# Schematic.net
KiCad netlist of a schematic drawn in Altium Designer
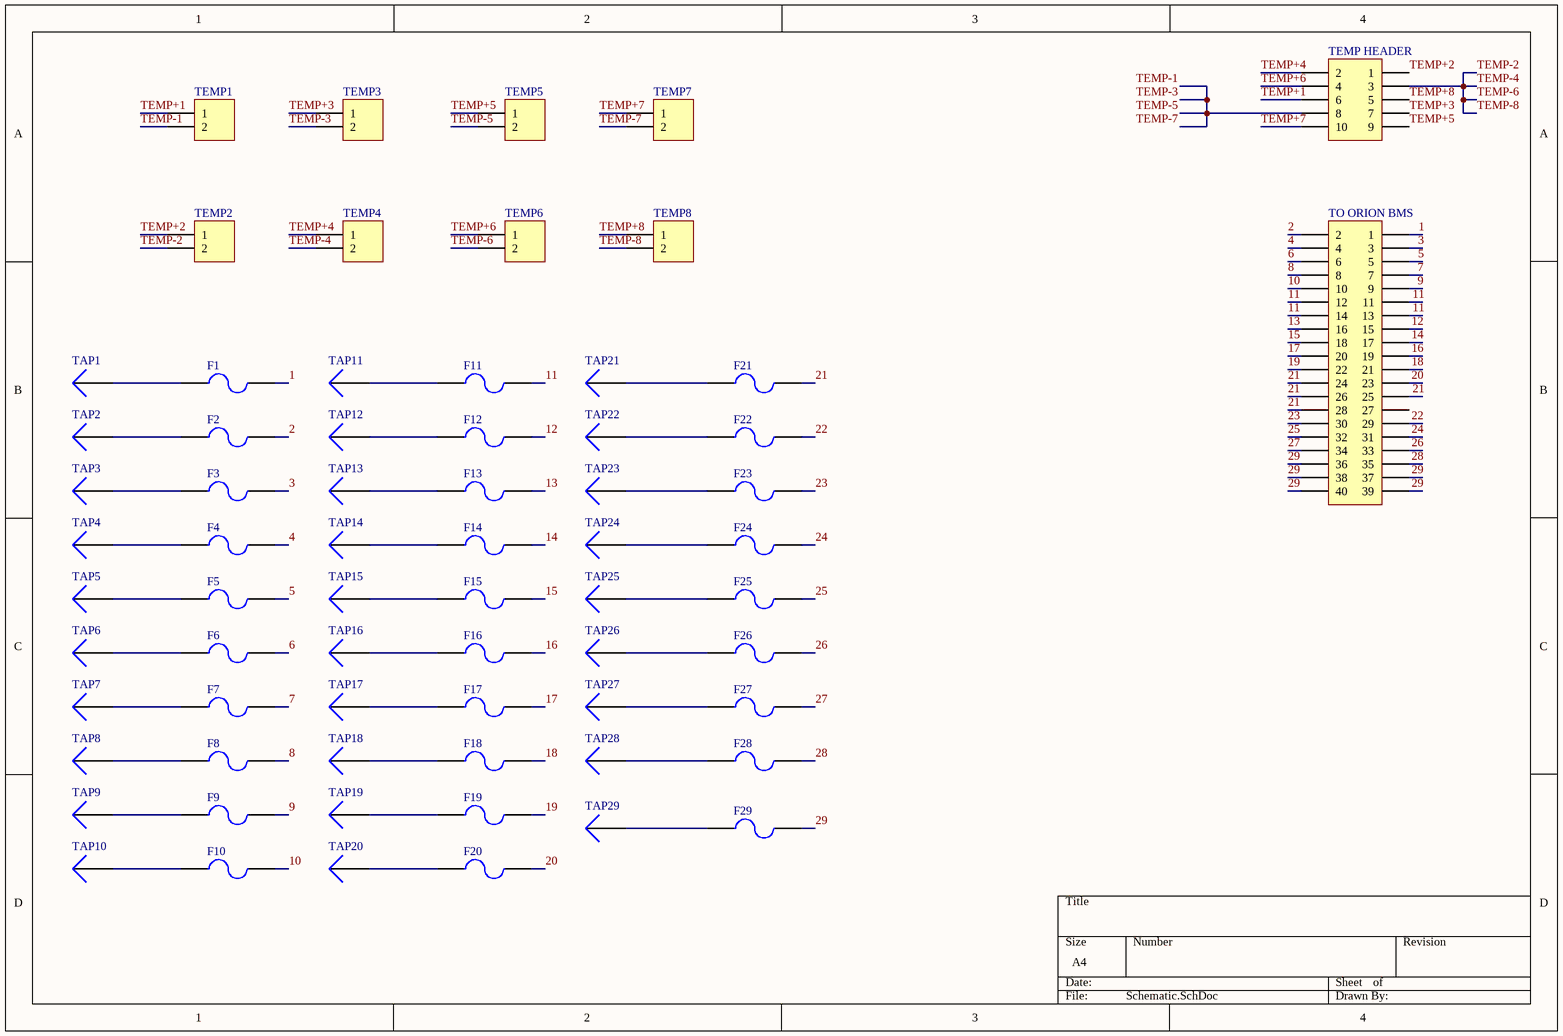
[diagram p0: Schematic.SchDoc]

(export (version "E")
  (design (tool "Eeschema 10.0.6"))
  (components
    (comp (ref "F1")
      (value "~")
      (footprint "0451Series_LTF")
      (description "FUSE BOARD MNT 750MA 125VAC/VDC")
      (fields (field (name "PART NUMBER") "0154.750MRL") (field (name "MANUFACTURER") "Littelfuse Inc."))
      (libsource (lib "ts_standard_library") (part "Fuse"))
    )
    (comp (ref "F2")
      (value "~")
      (footprint "0451Series_LTF")
      (description "FUSE BOARD MNT 750MA 125VAC/VDC")
      (fields (field (name "PART NUMBER") "0154.750MRL") (field (name "MANUFACTURER") "Littelfuse Inc."))
      (libsource (lib "ts_standard_library") (part "Fuse"))
    )
    (comp (ref "F3")
      (value "~")
      (footprint "0451Series_LTF")
      (description "FUSE BOARD MNT 750MA 125VAC/VDC")
      (fields (field (name "PART NUMBER") "0154.750MRL") (field (name "MANUFACTURER") "Littelfuse Inc."))
      (libsource (lib "ts_standard_library") (part "Fuse"))
    )
    (comp (ref "F4")
      (value "~")
      (footprint "0451Series_LTF")
      (description "FUSE BOARD MNT 750MA 125VAC/VDC")
      (fields (field (name "PART NUMBER") "0154.750MRL") (field (name "MANUFACTURER") "Littelfuse Inc."))
      (libsource (lib "ts_standard_library") (part "Fuse"))
    )
    (comp (ref "F5")
      (value "~")
      (footprint "0451Series_LTF")
      (description "FUSE BOARD MNT 750MA 125VAC/VDC")
      (fields (field (name "PART NUMBER") "0154.750MRL") (field (name "MANUFACTURER") "Littelfuse Inc."))
      (libsource (lib "ts_standard_library") (part "Fuse"))
    )
    (comp (ref "F6")
      (value "~")
      (footprint "0451Series_LTF")
      (description "FUSE BOARD MNT 750MA 125VAC/VDC")
      (fields (field (name "PART NUMBER") "0154.750MRL") (field (name "MANUFACTURER") "Littelfuse Inc."))
      (libsource (lib "ts_standard_library") (part "Fuse"))
    )
    (comp (ref "F7")
      (value "~")
      (footprint "0451Series_LTF")
      (description "FUSE BOARD MNT 750MA 125VAC/VDC")
      (fields (field (name "PART NUMBER") "0154.750MRL") (field (name "MANUFACTURER") "Littelfuse Inc."))
      (libsource (lib "ts_standard_library") (part "Fuse"))
    )
    (comp (ref "F8")
      (value "~")
      (footprint "0451Series_LTF")
      (description "FUSE BOARD MNT 750MA 125VAC/VDC")
      (fields (field (name "PART NUMBER") "0154.750MRL") (field (name "MANUFACTURER") "Littelfuse Inc."))
      (libsource (lib "ts_standard_library") (part "Fuse"))
    )
    (comp (ref "F9")
      (value "~")
      (footprint "0451Series_LTF")
      (description "FUSE BOARD MNT 750MA 125VAC/VDC")
      (fields (field (name "PART NUMBER") "0154.750MRL") (field (name "MANUFACTURER") "Littelfuse Inc."))
      (libsource (lib "ts_standard_library") (part "Fuse"))
    )
    (comp (ref "F10")
      (value "~")
      (footprint "0451Series_LTF")
      (description "FUSE BOARD MNT 750MA 125VAC/VDC")
      (fields (field (name "PART NUMBER") "0154.750MRL") (field (name "MANUFACTURER") "Littelfuse Inc."))
      (libsource (lib "ts_standard_library") (part "Fuse"))
    )
    (comp (ref "F11")
      (value "~")
      (footprint "0451Series_LTF")
      (description "FUSE BOARD MNT 750MA 125VAC/VDC")
      (fields (field (name "PART NUMBER") "0154.750MRL") (field (name "MANUFACTURER") "Littelfuse Inc."))
      (libsource (lib "ts_standard_library") (part "Fuse"))
    )
    (comp (ref "F12")
      (value "~")
      (footprint "0451Series_LTF")
      (description "FUSE BOARD MNT 750MA 125VAC/VDC")
      (fields (field (name "PART NUMBER") "0154.750MRL") (field (name "MANUFACTURER") "Littelfuse Inc."))
      (libsource (lib "ts_standard_library") (part "Fuse"))
    )
    (comp (ref "F13")
      (value "~")
      (footprint "0451Series_LTF")
      (description "FUSE BOARD MNT 750MA 125VAC/VDC")
      (fields (field (name "PART NUMBER") "0154.750MRL") (field (name "MANUFACTURER") "Littelfuse Inc."))
      (libsource (lib "ts_standard_library") (part "Fuse"))
    )
    (comp (ref "F14")
      (value "~")
      (footprint "0451Series_LTF")
      (description "FUSE BOARD MNT 750MA 125VAC/VDC")
      (fields (field (name "PART NUMBER") "0154.750MRL") (field (name "MANUFACTURER") "Littelfuse Inc."))
      (libsource (lib "ts_standard_library") (part "Fuse"))
    )
    (comp (ref "F15")
      (value "~")
      (footprint "0451Series_LTF")
      (description "FUSE BOARD MNT 750MA 125VAC/VDC")
      (fields (field (name "PART NUMBER") "0154.750MRL") (field (name "MANUFACTURER") "Littelfuse Inc."))
      (libsource (lib "ts_standard_library") (part "Fuse"))
    )
    (comp (ref "F16")
      (value "~")
      (footprint "0451Series_LTF")
      (description "FUSE BOARD MNT 750MA 125VAC/VDC")
      (fields (field (name "PART NUMBER") "0154.750MRL") (field (name "MANUFACTURER") "Littelfuse Inc."))
      (libsource (lib "ts_standard_library") (part "Fuse"))
    )
    (comp (ref "F17")
      (value "~")
      (footprint "0451Series_LTF")
      (description "FUSE BOARD MNT 750MA 125VAC/VDC")
      (fields (field (name "PART NUMBER") "0154.750MRL") (field (name "MANUFACTURER") "Littelfuse Inc."))
      (libsource (lib "ts_standard_library") (part "Fuse"))
    )
    (comp (ref "F18")
      (value "~")
      (footprint "0451Series_LTF")
      (description "FUSE BOARD MNT 750MA 125VAC/VDC")
      (fields (field (name "PART NUMBER") "0154.750MRL") (field (name "MANUFACTURER") "Littelfuse Inc."))
      (libsource (lib "ts_standard_library") (part "Fuse"))
    )
    (comp (ref "F19")
      (value "~")
      (footprint "0451Series_LTF")
      (description "FUSE BOARD MNT 750MA 125VAC/VDC")
      (fields (field (name "PART NUMBER") "0154.750MRL") (field (name "MANUFACTURER") "Littelfuse Inc."))
      (libsource (lib "ts_standard_library") (part "Fuse"))
    )
    (comp (ref "F20")
      (value "~")
      (footprint "0451Series_LTF")
      (description "FUSE BOARD MNT 750MA 125VAC/VDC")
      (fields (field (name "PART NUMBER") "0154.750MRL") (field (name "MANUFACTURER") "Littelfuse Inc."))
      (libsource (lib "ts_standard_library") (part "Fuse"))
    )
    (comp (ref "F21")
      (value "~")
      (footprint "0451Series_LTF")
      (description "FUSE BOARD MNT 750MA 125VAC/VDC")
      (fields (field (name "PART NUMBER") "0154.750MRL") (field (name "MANUFACTURER") "Littelfuse Inc."))
      (libsource (lib "ts_standard_library") (part "Fuse"))
    )
    (comp (ref "F22")
      (value "~")
      (footprint "0451Series_LTF")
      (description "FUSE BOARD MNT 750MA 125VAC/VDC")
      (fields (field (name "PART NUMBER") "0154.750MRL") (field (name "MANUFACTURER") "Littelfuse Inc."))
      (libsource (lib "ts_standard_library") (part "Fuse"))
    )
    (comp (ref "F23")
      (value "~")
      (footprint "0451Series_LTF")
      (description "FUSE BOARD MNT 750MA 125VAC/VDC")
      (fields (field (name "PART NUMBER") "0154.750MRL") (field (name "MANUFACTURER") "Littelfuse Inc."))
      (libsource (lib "ts_standard_library") (part "Fuse"))
    )
    (comp (ref "F24")
      (value "~")
      (footprint "0451Series_LTF")
      (description "FUSE BOARD MNT 750MA 125VAC/VDC")
      (fields (field (name "PART NUMBER") "0154.750MRL") (field (name "MANUFACTURER") "Littelfuse Inc."))
      (libsource (lib "ts_standard_library") (part "Fuse"))
    )
    (comp (ref "F25")
      (value "~")
      (footprint "0451Series_LTF")
      (description "FUSE BOARD MNT 750MA 125VAC/VDC")
      (fields (field (name "PART NUMBER") "0154.750MRL") (field (name "MANUFACTURER") "Littelfuse Inc."))
      (libsource (lib "ts_standard_library") (part "Fuse"))
    )
    (comp (ref "F26")
      (value "~")
      (footprint "0451Series_LTF")
      (description "FUSE BOARD MNT 750MA 125VAC/VDC")
      (fields (field (name "PART NUMBER") "0154.750MRL") (field (name "MANUFACTURER") "Littelfuse Inc."))
      (libsource (lib "ts_standard_library") (part "Fuse"))
    )
    (comp (ref "F27")
      (value "~")
      (footprint "0451Series_LTF")
      (description "FUSE BOARD MNT 750MA 125VAC/VDC")
      (fields (field (name "PART NUMBER") "0154.750MRL") (field (name "MANUFACTURER") "Littelfuse Inc."))
      (libsource (lib "ts_standard_library") (part "Fuse"))
    )
    (comp (ref "F28")
      (value "~")
      (footprint "0451Series_LTF")
      (description "FUSE BOARD MNT 750MA 125VAC/VDC")
      (fields (field (name "PART NUMBER") "0154.750MRL") (field (name "MANUFACTURER") "Littelfuse Inc."))
      (libsource (lib "ts_standard_library") (part "Fuse"))
    )
    (comp (ref "F29")
      (value "~")
      (footprint "0451Series_LTF")
      (description "FUSE BOARD MNT 750MA 125VAC/VDC")
      (fields (field (name "PART NUMBER") "0154.750MRL") (field (name "MANUFACTURER") "Littelfuse Inc."))
      (libsource (lib "ts_standard_library") (part "Fuse"))
    )
    (comp (ref "TAP1")
      (value "~")
      (footprint "S7051-42R")
      (fields
        (field (name "PART NUMBER") "S7051-42R")
        (field (name "DIGIKEY PART NUMBER") "952-1741-1-ND")
        (field (name "CONTACT") "Gold")
      )
      (libsource (lib "ts_standard_connectors") (part "S7051-42R"))
    )
    (comp (ref "TAP2")
      (value "~")
      (footprint "S7051-42R")
      (fields
        (field (name "PART NUMBER") "S7051-42R")
        (field (name "DIGIKEY PART NUMBER") "952-1741-1-ND")
        (field (name "CONTACT") "Gold")
      )
      (libsource (lib "ts_standard_connectors") (part "S7051-42R"))
    )
    (comp (ref "TAP3")
      (value "~")
      (footprint "S7051-42R")
      (fields
        (field (name "PART NUMBER") "S7051-42R")
        (field (name "DIGIKEY PART NUMBER") "952-1741-1-ND")
        (field (name "CONTACT") "Gold")
      )
      (libsource (lib "ts_standard_connectors") (part "S7051-42R"))
    )
    (comp (ref "TAP4")
      (value "~")
      (footprint "S7051-42R")
      (fields
        (field (name "PART NUMBER") "S7051-42R")
        (field (name "DIGIKEY PART NUMBER") "952-1741-1-ND")
        (field (name "CONTACT") "Gold")
      )
      (libsource (lib "ts_standard_connectors") (part "S7051-42R"))
    )
    (comp (ref "TAP5")
      (value "~")
      (footprint "S7051-42R")
      (fields
        (field (name "PART NUMBER") "S7051-42R")
        (field (name "DIGIKEY PART NUMBER") "952-1741-1-ND")
        (field (name "CONTACT") "Gold")
      )
      (libsource (lib "ts_standard_connectors") (part "S7051-42R"))
    )
    (comp (ref "TAP6")
      (value "~")
      (footprint "S7051-42R")
      (fields
        (field (name "PART NUMBER") "S7051-42R")
        (field (name "DIGIKEY PART NUMBER") "952-1741-1-ND")
        (field (name "CONTACT") "Gold")
      )
      (libsource (lib "ts_standard_connectors") (part "S7051-42R"))
    )
    (comp (ref "TAP7")
      (value "~")
      (footprint "S7051-42R")
      (fields
        (field (name "PART NUMBER") "S7051-42R")
        (field (name "DIGIKEY PART NUMBER") "952-1741-1-ND")
        (field (name "CONTACT") "Gold")
      )
      (libsource (lib "ts_standard_connectors") (part "S7051-42R"))
    )
    (comp (ref "TAP8")
      (value "~")
      (footprint "S7051-42R")
      (fields
        (field (name "PART NUMBER") "S7051-42R")
        (field (name "DIGIKEY PART NUMBER") "952-1741-1-ND")
        (field (name "CONTACT") "Gold")
      )
      (libsource (lib "ts_standard_connectors") (part "S7051-42R"))
    )
    (comp (ref "TAP9")
      (value "~")
      (footprint "S7051-42R")
      (fields
        (field (name "PART NUMBER") "S7051-42R")
        (field (name "DIGIKEY PART NUMBER") "952-1741-1-ND")
        (field (name "CONTACT") "Gold")
      )
      (libsource (lib "ts_standard_connectors") (part "S7051-42R"))
    )
    (comp (ref "TAP10")
      (value "~")
      (footprint "S7051-42R")
      (fields
        (field (name "PART NUMBER") "S7051-42R")
        (field (name "DIGIKEY PART NUMBER") "952-1741-1-ND")
        (field (name "CONTACT") "Gold")
      )
      (libsource (lib "ts_standard_connectors") (part "S7051-42R"))
    )
    (comp (ref "TAP11")
      (value "~")
      (footprint "S7051-42R")
      (fields
        (field (name "PART NUMBER") "S7051-42R")
        (field (name "DIGIKEY PART NUMBER") "952-1741-1-ND")
        (field (name "CONTACT") "Gold")
      )
      (libsource (lib "ts_standard_connectors") (part "S7051-42R"))
    )
    (comp (ref "TAP12")
      (value "~")
      (footprint "S7051-42R")
      (fields
        (field (name "PART NUMBER") "S7051-42R")
        (field (name "DIGIKEY PART NUMBER") "952-1741-1-ND")
        (field (name "CONTACT") "Gold")
      )
      (libsource (lib "ts_standard_connectors") (part "S7051-42R"))
    )
    (comp (ref "TAP13")
      (value "~")
      (footprint "S7051-42R")
      (fields
        (field (name "PART NUMBER") "S7051-42R")
        (field (name "DIGIKEY PART NUMBER") "952-1741-1-ND")
        (field (name "CONTACT") "Gold")
      )
      (libsource (lib "ts_standard_connectors") (part "S7051-42R"))
    )
    (comp (ref "TAP14")
      (value "~")
      (footprint "S7051-42R")
      (fields
        (field (name "PART NUMBER") "S7051-42R")
        (field (name "DIGIKEY PART NUMBER") "952-1741-1-ND")
        (field (name "CONTACT") "Gold")
      )
      (libsource (lib "ts_standard_connectors") (part "S7051-42R"))
    )
    (comp (ref "TAP15")
      (value "~")
      (footprint "S7051-42R")
      (fields
        (field (name "PART NUMBER") "S7051-42R")
        (field (name "DIGIKEY PART NUMBER") "952-1741-1-ND")
        (field (name "CONTACT") "Gold")
      )
      (libsource (lib "ts_standard_connectors") (part "S7051-42R"))
    )
    (comp (ref "TAP16")
      (value "~")
      (footprint "S7051-42R")
      (fields
        (field (name "PART NUMBER") "S7051-42R")
        (field (name "DIGIKEY PART NUMBER") "952-1741-1-ND")
        (field (name "CONTACT") "Gold")
      )
      (libsource (lib "ts_standard_connectors") (part "S7051-42R"))
    )
    (comp (ref "TAP17")
      (value "~")
      (footprint "S7051-42R")
      (fields
        (field (name "PART NUMBER") "S7051-42R")
        (field (name "DIGIKEY PART NUMBER") "952-1741-1-ND")
        (field (name "CONTACT") "Gold")
      )
      (libsource (lib "ts_standard_connectors") (part "S7051-42R"))
    )
    (comp (ref "TAP18")
      (value "~")
      (footprint "S7051-42R")
      (fields
        (field (name "PART NUMBER") "S7051-42R")
        (field (name "DIGIKEY PART NUMBER") "952-1741-1-ND")
        (field (name "CONTACT") "Gold")
      )
      (libsource (lib "ts_standard_connectors") (part "S7051-42R"))
    )
    (comp (ref "TAP19")
      (value "~")
      (footprint "S7051-42R")
      (fields
        (field (name "PART NUMBER") "S7051-42R")
        (field (name "DIGIKEY PART NUMBER") "952-1741-1-ND")
        (field (name "CONTACT") "Gold")
      )
      (libsource (lib "ts_standard_connectors") (part "S7051-42R"))
    )
    (comp (ref "TAP20")
      (value "~")
      (footprint "S7051-42R")
      (fields
        (field (name "PART NUMBER") "S7051-42R")
        (field (name "DIGIKEY PART NUMBER") "952-1741-1-ND")
        (field (name "CONTACT") "Gold")
      )
      (libsource (lib "ts_standard_connectors") (part "S7051-42R"))
    )
    (comp (ref "TAP21")
      (value "~")
      (footprint "S7051-42R")
      (fields
        (field (name "PART NUMBER") "S7051-42R")
        (field (name "DIGIKEY PART NUMBER") "952-1741-1-ND")
        (field (name "CONTACT") "Gold")
      )
      (libsource (lib "ts_standard_connectors") (part "S7051-42R"))
    )
    (comp (ref "TAP22")
      (value "~")
      (footprint "S7051-42R")
      (fields
        (field (name "PART NUMBER") "S7051-42R")
        (field (name "DIGIKEY PART NUMBER") "952-1741-1-ND")
        (field (name "CONTACT") "Gold")
      )
      (libsource (lib "ts_standard_connectors") (part "S7051-42R"))
    )
    (comp (ref "TAP23")
      (value "~")
      (footprint "S7051-42R")
      (fields
        (field (name "PART NUMBER") "S7051-42R")
        (field (name "DIGIKEY PART NUMBER") "952-1741-1-ND")
        (field (name "CONTACT") "Gold")
      )
      (libsource (lib "ts_standard_connectors") (part "S7051-42R"))
    )
    (comp (ref "TAP24")
      (value "~")
      (footprint "S7051-42R")
      (fields
        (field (name "PART NUMBER") "S7051-42R")
        (field (name "DIGIKEY PART NUMBER") "952-1741-1-ND")
        (field (name "CONTACT") "Gold")
      )
      (libsource (lib "ts_standard_connectors") (part "S7051-42R"))
    )
    (comp (ref "TAP25")
      (value "~")
      (footprint "S7051-42R")
      (fields
        (field (name "PART NUMBER") "S7051-42R")
        (field (name "DIGIKEY PART NUMBER") "952-1741-1-ND")
        (field (name "CONTACT") "Gold")
      )
      (libsource (lib "ts_standard_connectors") (part "S7051-42R"))
    )
    (comp (ref "TAP26")
      (value "~")
      (footprint "S7051-42R")
      (fields
        (field (name "PART NUMBER") "S7051-42R")
        (field (name "DIGIKEY PART NUMBER") "952-1741-1-ND")
        (field (name "CONTACT") "Gold")
      )
      (libsource (lib "ts_standard_connectors") (part "S7051-42R"))
    )
    (comp (ref "TAP27")
      (value "~")
      (footprint "S7051-42R")
      (fields
        (field (name "PART NUMBER") "S7051-42R")
        (field (name "DIGIKEY PART NUMBER") "952-1741-1-ND")
        (field (name "CONTACT") "Gold")
      )
      (libsource (lib "ts_standard_connectors") (part "S7051-42R"))
    )
    (comp (ref "TAP28")
      (value "~")
      (footprint "S7051-42R")
      (fields
        (field (name "PART NUMBER") "S7051-42R")
        (field (name "DIGIKEY PART NUMBER") "952-1741-1-ND")
        (field (name "CONTACT") "Gold")
      )
      (libsource (lib "ts_standard_connectors") (part "S7051-42R"))
    )
    (comp (ref "TAP29")
      (value "~")
      (footprint "S7051-42R")
      (fields
        (field (name "PART NUMBER") "S7051-42R")
        (field (name "DIGIKEY PART NUMBER") "952-1741-1-ND")
        (field (name "CONTACT") "Gold")
      )
      (libsource (lib "ts_standard_connectors") (part "S7051-42R"))
    )
    (comp (ref "TEMP HEADER")
      (value "~")
      (footprint "39288100")
      (fields
        (field (name "PART NUMBER") "39288100")
        (field (name "DIGIKEY PART NUMBER") "WM23804-ND")
        (field (name "CONTACT") "Tin")
      )
      (libsource (lib "ts_standard_connectors") (part "10"))
    )
    (comp (ref "TEMP1")
      (value "~")
      (footprint "S2B-XH-A(LF)(SN)")
      (fields
        (field (name "PART NUMBER") "S2B-XH-A(LF)(SN)")
        (field (name "DIGIKEY PART NUMBER") "455-2257-ND")
        (field (name "CONTACT") "NA")
      )
      (libsource (lib "ts_standard_connectors") (part "Header 1x2"))
    )
    (comp (ref "TEMP2")
      (value "~")
      (footprint "S2B-XH-A(LF)(SN)")
      (fields
        (field (name "PART NUMBER") "S2B-XH-A(LF)(SN)")
        (field (name "DIGIKEY PART NUMBER") "455-2257-ND")
        (field (name "CONTACT") "NA")
      )
      (libsource (lib "ts_standard_connectors") (part "Header 1x2"))
    )
    (comp (ref "TEMP3")
      (value "~")
      (footprint "S2B-XH-A(LF)(SN)")
      (fields
        (field (name "PART NUMBER") "S2B-XH-A(LF)(SN)")
        (field (name "DIGIKEY PART NUMBER") "455-2257-ND")
        (field (name "CONTACT") "NA")
      )
      (libsource (lib "ts_standard_connectors") (part "Header 1x2"))
    )
    (comp (ref "TEMP4")
      (value "~")
      (footprint "S2B-XH-A(LF)(SN)")
      (fields
        (field (name "PART NUMBER") "S2B-XH-A(LF)(SN)")
        (field (name "DIGIKEY PART NUMBER") "455-2257-ND")
        (field (name "CONTACT") "NA")
      )
      (libsource (lib "ts_standard_connectors") (part "Header 1x2"))
    )
    (comp (ref "TEMP5")
      (value "~")
      (footprint "S2B-XH-A(LF)(SN)")
      (fields
        (field (name "PART NUMBER") "S2B-XH-A(LF)(SN)")
        (field (name "DIGIKEY PART NUMBER") "455-2257-ND")
        (field (name "CONTACT") "NA")
      )
      (libsource (lib "ts_standard_connectors") (part "Header 1x2"))
    )
    (comp (ref "TEMP6")
      (value "~")
      (footprint "S2B-XH-A(LF)(SN)")
      (fields
        (field (name "PART NUMBER") "S2B-XH-A(LF)(SN)")
        (field (name "DIGIKEY PART NUMBER") "455-2257-ND")
        (field (name "CONTACT") "NA")
      )
      (libsource (lib "ts_standard_connectors") (part "Header 1x2"))
    )
    (comp (ref "TEMP7")
      (value "~")
      (footprint "S2B-XH-A(LF)(SN)")
      (fields
        (field (name "PART NUMBER") "S2B-XH-A(LF)(SN)")
        (field (name "DIGIKEY PART NUMBER") "455-2257-ND")
        (field (name "CONTACT") "NA")
      )
      (libsource (lib "ts_standard_connectors") (part "Header 1x2"))
    )
    (comp (ref "TEMP8")
      (value "~")
      (footprint "S2B-XH-A(LF)(SN)")
      (fields
        (field (name "PART NUMBER") "S2B-XH-A(LF)(SN)")
        (field (name "DIGIKEY PART NUMBER") "455-2257-ND")
        (field (name "CONTACT") "NA")
      )
      (libsource (lib "ts_standard_connectors") (part "Header 1x2"))
    )
    (comp (ref "TO ORION BMS")
      (value "~")
      (footprint "1376113-6")
      (fields
        (field (name "PART NUMBER") "1376113-6")
        (field (name "DIGIKEY PART NUMBER") "1376113-6-ND")
        (field (name "CONTACT") "Gold")
      )
      (libsource (lib "ts_standard_connectors") (part "1376113-6"))
    )
  )
  (nets
    (net (code "1") (name "/1") (class "Default")
      (node (ref "F1") (pin "2") (pinfunction "2_2") (pintype "passive"))
      (node (ref "TO ORION BMS") (pin "1") (pinfunction "1_1") (pintype "passive"))
    )
    (net (code "2") (name "/2") (class "Default")
      (node (ref "F2") (pin "2") (pinfunction "2_2") (pintype "passive"))
      (node (ref "TO ORION BMS") (pin "2") (pinfunction "2_2") (pintype "passive"))
    )
    (net (code "3") (name "/3") (class "Default")
      (node (ref "F3") (pin "2") (pinfunction "2_2") (pintype "passive"))
      (node (ref "TO ORION BMS") (pin "3") (pinfunction "3_3") (pintype "passive"))
    )
    (net (code "4") (name "/4") (class "Default")
      (node (ref "F4") (pin "2") (pinfunction "2_2") (pintype "passive"))
      (node (ref "TO ORION BMS") (pin "4") (pinfunction "4_4") (pintype "passive"))
    )
    (net (code "5") (name "/5") (class "Default")
      (node (ref "F5") (pin "2") (pinfunction "2_2") (pintype "passive"))
      (node (ref "TO ORION BMS") (pin "5") (pinfunction "5_5") (pintype "passive"))
    )
    (net (code "6") (name "/6") (class "Default")
      (node (ref "F6") (pin "2") (pinfunction "2_2") (pintype "passive"))
      (node (ref "TO ORION BMS") (pin "6") (pinfunction "6_6") (pintype "passive"))
    )
    (net (code "7") (name "/7") (class "Default")
      (node (ref "F7") (pin "2") (pinfunction "2_2") (pintype "passive"))
      (node (ref "TO ORION BMS") (pin "7") (pinfunction "7_7") (pintype "passive"))
    )
    (net (code "8") (name "/8") (class "Default")
      (node (ref "F8") (pin "2") (pinfunction "2_2") (pintype "passive"))
      (node (ref "TO ORION BMS") (pin "8") (pinfunction "8_8") (pintype "passive"))
    )
    (net (code "9") (name "/9") (class "Default")
      (node (ref "F9") (pin "2") (pinfunction "2_2") (pintype "passive"))
      (node (ref "TO ORION BMS") (pin "9") (pinfunction "9_9") (pintype "passive"))
    )
    (net (code "10") (name "/10") (class "Default")
      (node (ref "F10") (pin "2") (pinfunction "2_2") (pintype "passive"))
      (node (ref "TO ORION BMS") (pin "10") (pinfunction "10_10") (pintype "passive"))
    )
    (net (code "11") (name "/11") (class "Default")
      (node (ref "F11") (pin "2") (pinfunction "2_2") (pintype "passive"))
      (node (ref "TO ORION BMS") (pin "11") (pinfunction "11_11") (pintype "passive"))
      (node (ref "TO ORION BMS") (pin "12") (pinfunction "12_12") (pintype "passive"))
      (node (ref "TO ORION BMS") (pin "13") (pinfunction "13_13") (pintype "passive"))
      (node (ref "TO ORION BMS") (pin "14") (pinfunction "14_14") (pintype "passive"))
    )
    (net (code "12") (name "/12") (class "Default")
      (node (ref "F12") (pin "2") (pinfunction "2_2") (pintype "passive"))
      (node (ref "TO ORION BMS") (pin "15") (pinfunction "15_15") (pintype "passive"))
    )
    (net (code "13") (name "/13") (class "Default")
      (node (ref "F13") (pin "2") (pinfunction "2_2") (pintype "passive"))
      (node (ref "TO ORION BMS") (pin "16") (pinfunction "16_16") (pintype "passive"))
    )
    (net (code "14") (name "/14") (class "Default")
      (node (ref "F14") (pin "2") (pinfunction "2_2") (pintype "passive"))
      (node (ref "TO ORION BMS") (pin "17") (pinfunction "17_17") (pintype "passive"))
    )
    (net (code "15") (name "/15") (class "Default")
      (node (ref "F15") (pin "2") (pinfunction "2_2") (pintype "passive"))
      (node (ref "TO ORION BMS") (pin "18") (pinfunction "18_18") (pintype "passive"))
    )
    (net (code "16") (name "/16") (class "Default")
      (node (ref "F16") (pin "2") (pinfunction "2_2") (pintype "passive"))
      (node (ref "TO ORION BMS") (pin "19") (pinfunction "19_19") (pintype "passive"))
    )
    (net (code "17") (name "/17") (class "Default")
      (node (ref "F17") (pin "2") (pinfunction "2_2") (pintype "passive"))
      (node (ref "TO ORION BMS") (pin "20") (pinfunction "20_20") (pintype "passive"))
    )
    (net (code "18") (name "/18") (class "Default")
      (node (ref "F18") (pin "2") (pinfunction "2_2") (pintype "passive"))
      (node (ref "TO ORION BMS") (pin "21") (pinfunction "21_21") (pintype "passive"))
    )
    (net (code "19") (name "/19") (class "Default")
      (node (ref "F19") (pin "2") (pinfunction "2_2") (pintype "passive"))
      (node (ref "TO ORION BMS") (pin "22") (pinfunction "22_22") (pintype "passive"))
    )
    (net (code "20") (name "/20") (class "Default")
      (node (ref "F20") (pin "2") (pinfunction "2_2") (pintype "passive"))
      (node (ref "TO ORION BMS") (pin "23") (pinfunction "23_23") (pintype "passive"))
    )
    (net (code "21") (name "/21") (class "Default")
      (node (ref "F21") (pin "2") (pinfunction "2_2") (pintype "passive"))
      (node (ref "TO ORION BMS") (pin "24") (pinfunction "24_24") (pintype "passive"))
      (node (ref "TO ORION BMS") (pin "25") (pinfunction "25_25") (pintype "passive"))
      (node (ref "TO ORION BMS") (pin "26") (pinfunction "26_26") (pintype "passive"))
      (node (ref "TO ORION BMS") (pin "28") (pinfunction "28_28") (pintype "passive"))
    )
    (net (code "22") (name "/22") (class "Default")
      (node (ref "F22") (pin "2") (pinfunction "2_2") (pintype "passive"))
      (node (ref "TO ORION BMS") (pin "29") (pinfunction "29_29") (pintype "passive"))
    )
    (net (code "23") (name "/23") (class "Default")
      (node (ref "F23") (pin "2") (pinfunction "2_2") (pintype "passive"))
      (node (ref "TO ORION BMS") (pin "30") (pinfunction "30_30") (pintype "passive"))
    )
    (net (code "24") (name "/24") (class "Default")
      (node (ref "F24") (pin "2") (pinfunction "2_2") (pintype "passive"))
      (node (ref "TO ORION BMS") (pin "31") (pinfunction "31_31") (pintype "passive"))
    )
    (net (code "25") (name "/25") (class "Default")
      (node (ref "F25") (pin "2") (pinfunction "2_2") (pintype "passive"))
      (node (ref "TO ORION BMS") (pin "32") (pinfunction "32_32") (pintype "passive"))
    )
    (net (code "26") (name "/26") (class "Default")
      (node (ref "F26") (pin "2") (pinfunction "2_2") (pintype "passive"))
      (node (ref "TO ORION BMS") (pin "33") (pinfunction "33_33") (pintype "passive"))
    )
    (net (code "27") (name "/27") (class "Default")
      (node (ref "F27") (pin "2") (pinfunction "2_2") (pintype "passive"))
      (node (ref "TO ORION BMS") (pin "34") (pinfunction "34_34") (pintype "passive"))
    )
    (net (code "28") (name "/28") (class "Default")
      (node (ref "F28") (pin "2") (pinfunction "2_2") (pintype "passive"))
      (node (ref "TO ORION BMS") (pin "35") (pinfunction "35_35") (pintype "passive"))
    )
    (net (code "29") (name "/29") (class "Default")
      (node (ref "F29") (pin "2") (pinfunction "2_2") (pintype "passive"))
      (node (ref "TO ORION BMS") (pin "36") (pinfunction "36_36") (pintype "passive"))
      (node (ref "TO ORION BMS") (pin "37") (pinfunction "37_37") (pintype "passive"))
      (node (ref "TO ORION BMS") (pin "38") (pinfunction "38_38") (pintype "passive"))
      (node (ref "TO ORION BMS") (pin "39") (pinfunction "39_39") (pintype "passive"))
      (node (ref "TO ORION BMS") (pin "40") (pinfunction "40_40") (pintype "passive"))
    )
    (net (code "30") (name "/TEMP+1") (class "Default")
      (node (ref "TEMP HEADER") (pin "6") (pinfunction "6_6") (pintype "passive"))
      (node (ref "TEMP1") (pin "1") (pinfunction "1_1") (pintype "passive"))
    )
    (net (code "31") (name "/TEMP+2") (class "Default")
      (node (ref "TEMP HEADER") (pin "1") (pinfunction "1_1") (pintype "passive"))
      (node (ref "TEMP2") (pin "1") (pinfunction "1_1") (pintype "passive"))
    )
    (net (code "32") (name "/TEMP+3") (class "Default")
      (node (ref "TEMP HEADER") (pin "7") (pinfunction "7_7") (pintype "passive"))
      (node (ref "TEMP3") (pin "1") (pinfunction "1_1") (pintype "passive"))
    )
    (net (code "33") (name "/TEMP+4") (class "Default")
      (node (ref "TEMP HEADER") (pin "2") (pinfunction "2_2") (pintype "passive"))
      (node (ref "TEMP4") (pin "1") (pinfunction "1_1") (pintype "passive"))
    )
    (net (code "34") (name "/TEMP+5") (class "Default")
      (node (ref "TEMP HEADER") (pin "9") (pinfunction "9_9") (pintype "passive"))
      (node (ref "TEMP5") (pin "1") (pinfunction "1_1") (pintype "passive"))
    )
    (net (code "35") (name "/TEMP+6") (class "Default")
      (node (ref "TEMP HEADER") (pin "4") (pinfunction "4_4") (pintype "passive"))
      (node (ref "TEMP6") (pin "1") (pinfunction "1_1") (pintype "passive"))
    )
    (net (code "36") (name "/TEMP+7") (class "Default")
      (node (ref "TEMP HEADER") (pin "10") (pinfunction "10_10") (pintype "passive"))
      (node (ref "TEMP7") (pin "1") (pinfunction "1_1") (pintype "passive"))
    )
    (net (code "37") (name "/TEMP+8") (class "Default")
      (node (ref "TEMP HEADER") (pin "5") (pinfunction "5_5") (pintype "passive"))
      (node (ref "TEMP8") (pin "1") (pinfunction "1_1") (pintype "passive"))
    )
    (net (code "38") (name "/TEMP-1") (class "Default")
      (node (ref "TEMP HEADER") (pin "8") (pinfunction "8_8") (pintype "passive"))
      (node (ref "TEMP1") (pin "2") (pinfunction "2_2") (pintype "passive"))
      (node (ref "TEMP3") (pin "2") (pinfunction "2_2") (pintype "passive"))
      (node (ref "TEMP5") (pin "2") (pinfunction "2_2") (pintype "passive"))
      (node (ref "TEMP7") (pin "2") (pinfunction "2_2") (pintype "passive"))
    )
    (net (code "39") (name "/TEMP-2") (class "Default")
      (node (ref "TEMP HEADER") (pin "3") (pinfunction "3_3") (pintype "passive"))
      (node (ref "TEMP2") (pin "2") (pinfunction "2_2") (pintype "passive"))
      (node (ref "TEMP4") (pin "2") (pinfunction "2_2") (pintype "passive"))
      (node (ref "TEMP6") (pin "2") (pinfunction "2_2") (pintype "passive"))
      (node (ref "TEMP8") (pin "2") (pinfunction "2_2") (pintype "passive"))
    )
    (net (code "40") (name "Net-(TAP1-=\"part_number\")") (class "Default")
      (node (ref "F1") (pin "1") (pinfunction "1_1") (pintype "passive"))
      (node (ref "TAP1") (pin "1") (pinfunction "=\"part_number\"_1") (pintype "passive"))
    )
    (net (code "41") (name "Net-(TAP2-=\"part_number\")") (class "Default")
      (node (ref "F2") (pin "1") (pinfunction "1_1") (pintype "passive"))
      (node (ref "TAP2") (pin "1") (pinfunction "=\"part_number\"_1") (pintype "passive"))
    )
    (net (code "42") (name "Net-(TAP3-=\"part_number\")") (class "Default")
      (node (ref "F3") (pin "1") (pinfunction "1_1") (pintype "passive"))
      (node (ref "TAP3") (pin "1") (pinfunction "=\"part_number\"_1") (pintype "passive"))
    )
    (net (code "43") (name "Net-(TAP4-=\"part_number\")") (class "Default")
      (node (ref "F4") (pin "1") (pinfunction "1_1") (pintype "passive"))
      (node (ref "TAP4") (pin "1") (pinfunction "=\"part_number\"_1") (pintype "passive"))
    )
    (net (code "44") (name "Net-(TAP5-=\"part_number\")") (class "Default")
      (node (ref "F5") (pin "1") (pinfunction "1_1") (pintype "passive"))
      (node (ref "TAP5") (pin "1") (pinfunction "=\"part_number\"_1") (pintype "passive"))
    )
    (net (code "45") (name "Net-(TAP6-=\"part_number\")") (class "Default")
      (node (ref "F6") (pin "1") (pinfunction "1_1") (pintype "passive"))
      (node (ref "TAP6") (pin "1") (pinfunction "=\"part_number\"_1") (pintype "passive"))
    )
    (net (code "46") (name "Net-(TAP7-=\"part_number\")") (class "Default")
      (node (ref "F7") (pin "1") (pinfunction "1_1") (pintype "passive"))
      (node (ref "TAP7") (pin "1") (pinfunction "=\"part_number\"_1") (pintype "passive"))
    )
    (net (code "47") (name "Net-(TAP8-=\"part_number\")") (class "Default")
      (node (ref "F8") (pin "1") (pinfunction "1_1") (pintype "passive"))
      (node (ref "TAP8") (pin "1") (pinfunction "=\"part_number\"_1") (pintype "passive"))
    )
    (net (code "48") (name "Net-(TAP9-=\"part_number\")") (class "Default")
      (node (ref "F9") (pin "1") (pinfunction "1_1") (pintype "passive"))
      (node (ref "TAP9") (pin "1") (pinfunction "=\"part_number\"_1") (pintype "passive"))
    )
    (net (code "49") (name "Net-(TAP10-=\"part_number\")") (class "Default")
      (node (ref "F10") (pin "1") (pinfunction "1_1") (pintype "passive"))
      (node (ref "TAP10") (pin "1") (pinfunction "=\"part_number\"_1") (pintype "passive"))
    )
    (net (code "50") (name "Net-(TAP11-=\"part_number\")") (class "Default")
      (node (ref "F11") (pin "1") (pinfunction "1_1") (pintype "passive"))
      (node (ref "TAP11") (pin "1") (pinfunction "=\"part_number\"_1") (pintype "passive"))
    )
    (net (code "51") (name "Net-(TAP12-=\"part_number\")") (class "Default")
      (node (ref "F12") (pin "1") (pinfunction "1_1") (pintype "passive"))
      (node (ref "TAP12") (pin "1") (pinfunction "=\"part_number\"_1") (pintype "passive"))
    )
    (net (code "52") (name "Net-(TAP13-=\"part_number\")") (class "Default")
      (node (ref "F13") (pin "1") (pinfunction "1_1") (pintype "passive"))
      (node (ref "TAP13") (pin "1") (pinfunction "=\"part_number\"_1") (pintype "passive"))
    )
    (net (code "53") (name "Net-(TAP14-=\"part_number\")") (class "Default")
      (node (ref "F14") (pin "1") (pinfunction "1_1") (pintype "passive"))
      (node (ref "TAP14") (pin "1") (pinfunction "=\"part_number\"_1") (pintype "passive"))
    )
    (net (code "54") (name "Net-(TAP15-=\"part_number\")") (class "Default")
      (node (ref "F15") (pin "1") (pinfunction "1_1") (pintype "passive"))
      (node (ref "TAP15") (pin "1") (pinfunction "=\"part_number\"_1") (pintype "passive"))
    )
    (net (code "55") (name "Net-(TAP16-=\"part_number\")") (class "Default")
      (node (ref "F16") (pin "1") (pinfunction "1_1") (pintype "passive"))
      (node (ref "TAP16") (pin "1") (pinfunction "=\"part_number\"_1") (pintype "passive"))
    )
    (net (code "56") (name "Net-(TAP17-=\"part_number\")") (class "Default")
      (node (ref "F17") (pin "1") (pinfunction "1_1") (pintype "passive"))
      (node (ref "TAP17") (pin "1") (pinfunction "=\"part_number\"_1") (pintype "passive"))
    )
    (net (code "57") (name "Net-(TAP18-=\"part_number\")") (class "Default")
      (node (ref "F18") (pin "1") (pinfunction "1_1") (pintype "passive"))
      (node (ref "TAP18") (pin "1") (pinfunction "=\"part_number\"_1") (pintype "passive"))
    )
    (net (code "58") (name "Net-(TAP19-=\"part_number\")") (class "Default")
      (node (ref "F19") (pin "1") (pinfunction "1_1") (pintype "passive"))
      (node (ref "TAP19") (pin "1") (pinfunction "=\"part_number\"_1") (pintype "passive"))
    )
    (net (code "59") (name "Net-(TAP20-=\"part_number\")") (class "Default")
      (node (ref "F20") (pin "1") (pinfunction "1_1") (pintype "passive"))
      (node (ref "TAP20") (pin "1") (pinfunction "=\"part_number\"_1") (pintype "passive"))
    )
    (net (code "60") (name "Net-(TAP21-=\"part_number\")") (class "Default")
      (node (ref "F21") (pin "1") (pinfunction "1_1") (pintype "passive"))
      (node (ref "TAP21") (pin "1") (pinfunction "=\"part_number\"_1") (pintype "passive"))
    )
    (net (code "61") (name "Net-(TAP22-=\"part_number\")") (class "Default")
      (node (ref "F22") (pin "1") (pinfunction "1_1") (pintype "passive"))
      (node (ref "TAP22") (pin "1") (pinfunction "=\"part_number\"_1") (pintype "passive"))
    )
    (net (code "62") (name "Net-(TAP23-=\"part_number\")") (class "Default")
      (node (ref "F23") (pin "1") (pinfunction "1_1") (pintype "passive"))
      (node (ref "TAP23") (pin "1") (pinfunction "=\"part_number\"_1") (pintype "passive"))
    )
    (net (code "63") (name "Net-(TAP24-=\"part_number\")") (class "Default")
      (node (ref "F24") (pin "1") (pinfunction "1_1") (pintype "passive"))
      (node (ref "TAP24") (pin "1") (pinfunction "=\"part_number\"_1") (pintype "passive"))
    )
    (net (code "64") (name "Net-(TAP25-=\"part_number\")") (class "Default")
      (node (ref "F25") (pin "1") (pinfunction "1_1") (pintype "passive"))
      (node (ref "TAP25") (pin "1") (pinfunction "=\"part_number\"_1") (pintype "passive"))
    )
    (net (code "65") (name "Net-(TAP26-=\"part_number\")") (class "Default")
      (node (ref "F26") (pin "1") (pinfunction "1_1") (pintype "passive"))
      (node (ref "TAP26") (pin "1") (pinfunction "=\"part_number\"_1") (pintype "passive"))
    )
    (net (code "66") (name "Net-(TAP27-=\"part_number\")") (class "Default")
      (node (ref "F27") (pin "1") (pinfunction "1_1") (pintype "passive"))
      (node (ref "TAP27") (pin "1") (pinfunction "=\"part_number\"_1") (pintype "passive"))
    )
    (net (code "67") (name "Net-(TAP28-=\"part_number\")") (class "Default")
      (node (ref "F28") (pin "1") (pinfunction "1_1") (pintype "passive"))
      (node (ref "TAP28") (pin "1") (pinfunction "=\"part_number\"_1") (pintype "passive"))
    )
    (net (code "68") (name "Net-(TAP29-=\"part_number\")") (class "Default")
      (node (ref "F29") (pin "1") (pinfunction "1_1") (pintype "passive"))
      (node (ref "TAP29") (pin "1") (pinfunction "=\"part_number\"_1") (pintype "passive"))
    )
    (net (code "69") (name "unconnected-(TO ORION BMS-Pad27)") (class "Default")
      (node (ref "TO ORION BMS") (pin "27") (pinfunction "27_27") (pintype "passive"))
    )
  )
)
